# super-nintendo-forever.net
KiCad netlist of a schematic drawn in EAGLE
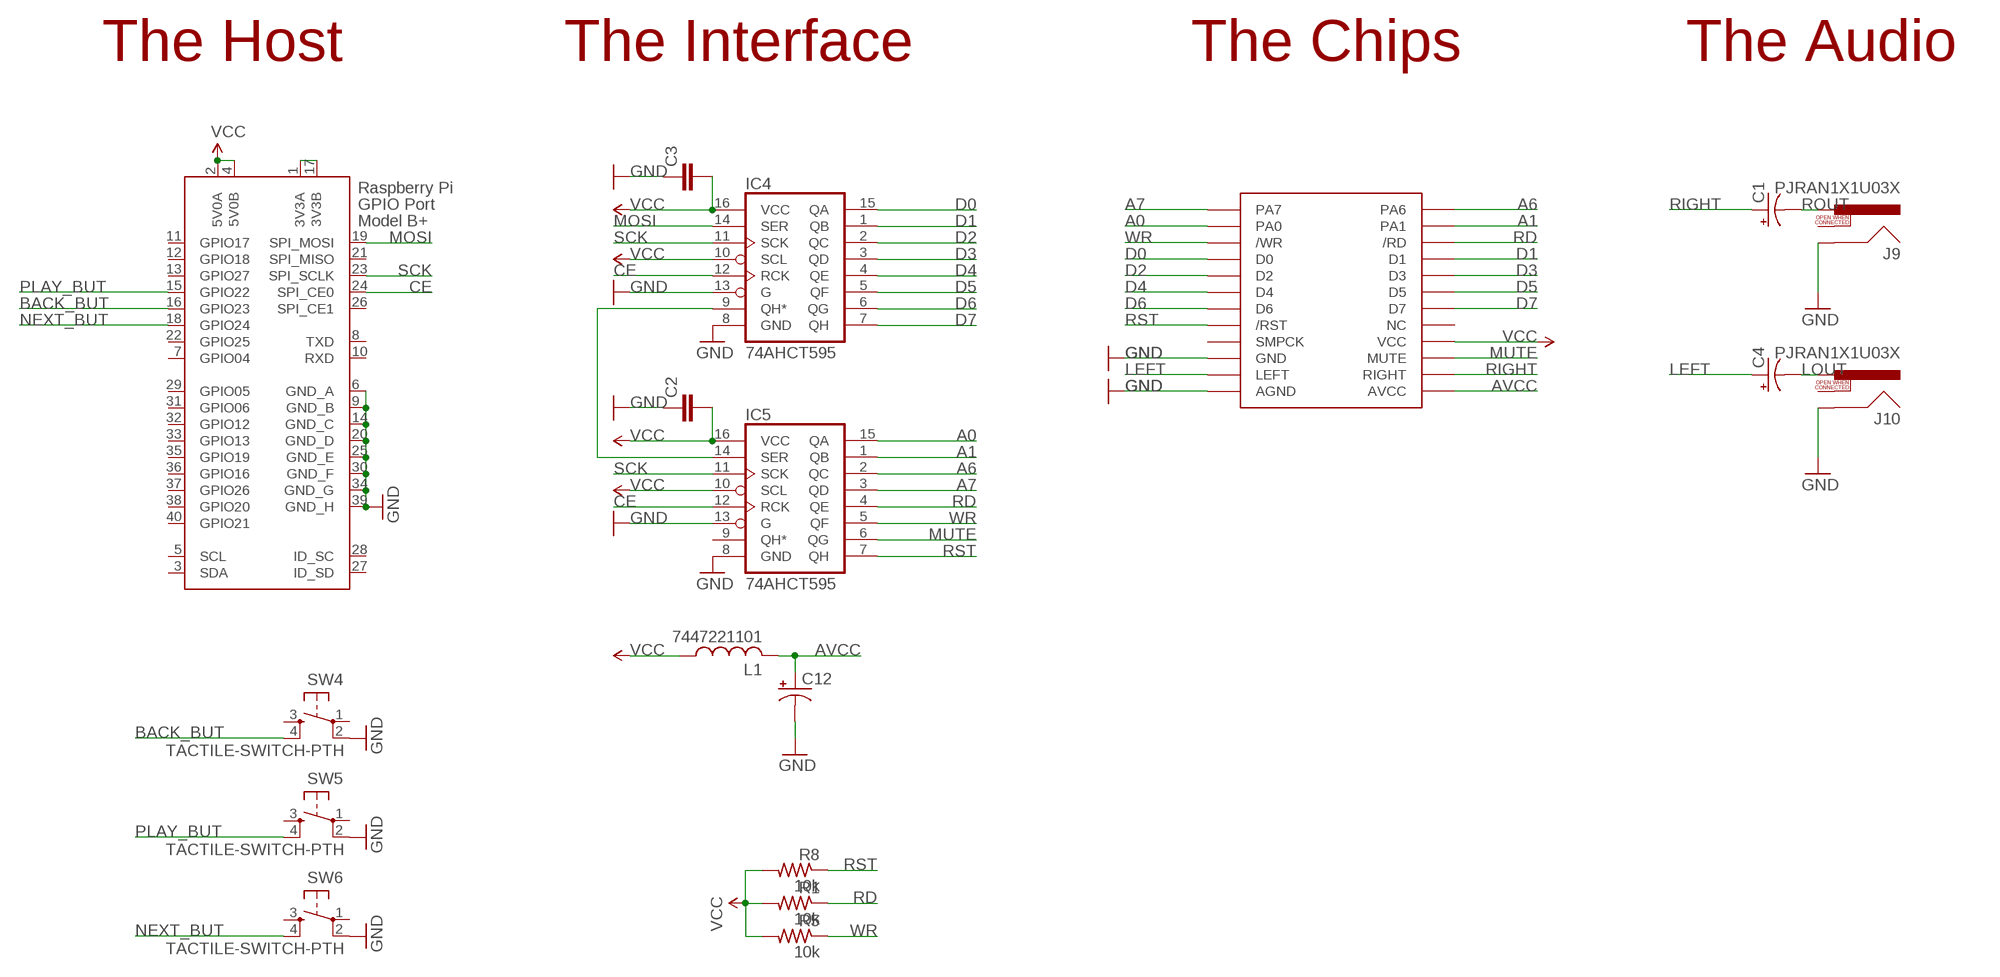
[diagram p0: schematic, sheet 1]

(export (version "E")
  (design (tool "Eeschema 10.0.6"))
  (components
    (comp (ref "C1")
      (value "CPOL-USE2-4")
      (footprint "eagle-import:E2-4")
      (libsource (lib "eagle-import") (part "CPOL-USE2-4"))
    )
    (comp (ref "C2")
      (value "C-EU025-024X044")
      (footprint "eagle-import:C025-024X044")
      (libsource (lib "eagle-import") (part "C-EU025-024X044"))
    )
    (comp (ref "C3")
      (value "C-EU025-024X044")
      (footprint "eagle-import:C025-024X044")
      (libsource (lib "eagle-import") (part "C-EU025-024X044"))
    )
    (comp (ref "C4")
      (value "CPOL-USE2-4")
      (footprint "eagle-import:E2-4")
      (libsource (lib "eagle-import") (part "CPOL-USE2-4"))
    )
    (comp (ref "C12")
      (value "CPOL-USE2-4")
      (footprint "eagle-import:E2-4")
      (libsource (lib "eagle-import") (part "CPOL-USE2-4"))
    )
    (comp (ref "IC4")
      (value "74AHCT595")
      (footprint "eagle-import:DIL16")
      (libsource (lib "eagle-import") (part "74595NLS"))
    )
    (comp (ref "IC5")
      (value "74AHCT595")
      (footprint "eagle-import:DIL16")
      (libsource (lib "eagle-import") (part "74595NLS"))
    )
    (comp (ref "J9")
      (value "PJRAN1X1U03X")
      (footprint "eagle-import:RCA")
      (libsource (lib "eagle-import") (part "RCA"))
    )
    (comp (ref "J10")
      (value "PJRAN1X1U03X")
      (footprint "eagle-import:RCA")
      (libsource (lib "eagle-import") (part "RCA"))
    )
    (comp (ref "L1")
      (value "7447221101")
      (footprint "eagle-import:12MMINDUCTOR")
      (libsource (lib "eagle-import") (part "L"))
    )
    (comp (ref "R1")
      (value "10k")
      (footprint "eagle-import:0207_7")
      (libsource (lib "eagle-import") (part "R-US_0207/7"))
    )
    (comp (ref "R5")
      (value "10k")
      (footprint "eagle-import:0207_7")
      (libsource (lib "eagle-import") (part "R-US_0207/7"))
    )
    (comp (ref "R8")
      (value "10k")
      (footprint "eagle-import:0207_7")
      (libsource (lib "eagle-import") (part "R-US_0207/7"))
    )
    (comp (ref "SW4")
      (value "TACTILE-SWITCH-PTH")
      (footprint "eagle-import:TAC-SWITCH-PTH")
      (libsource (lib "eagle-import") (part "TACTILE-SWITCH-PTH"))
    )
    (comp (ref "SW5")
      (value "TACTILE-SWITCH-PTH")
      (footprint "eagle-import:TAC-SWITCH-PTH")
      (libsource (lib "eagle-import") (part "TACTILE-SWITCH-PTH"))
    )
    (comp (ref "SW6")
      (value "TACTILE-SWITCH-PTH")
      (footprint "eagle-import:TAC-SWITCH-PTH")
      (libsource (lib "eagle-import") (part "TACTILE-SWITCH-PTH"))
    )
    (comp (ref "U$1")
      (value "APU2")
      (footprint "eagle-import:APU3")
      (libsource (lib "eagle-import") (part "APU2"))
    )
    (comp (ref "X2")
      (value "RASPI_BOARD_B+#_E4")
      (footprint "eagle-import:RASPI_BOARD_B+_EDGES_4DRILL")
      (libsource (lib "eagle-import") (part "RASPI_BOARD_B+#_E4"))
    )
  )
  (nets
    (net (code "1") (name "/A0") (class "Default")
      (node (ref "IC5") (pin "15") (pinfunction "QA_15") (pintype "tri_state"))
      (node (ref "U$1") (pin "A0") (pinfunction "PA0_A0") (pintype "bidirectional"))
    )
    (net (code "2") (name "/A1") (class "Default")
      (node (ref "IC5") (pin "1") (pinfunction "QB_1") (pintype "tri_state"))
      (node (ref "U$1") (pin "PA1") (pinfunction "PA1_PA1") (pintype "bidirectional"))
    )
    (net (code "3") (name "/A6") (class "Default")
      (node (ref "IC5") (pin "2") (pinfunction "QC_2") (pintype "tri_state"))
      (node (ref "U$1") (pin "PA6") (pinfunction "PA6_PA6") (pintype "bidirectional"))
    )
    (net (code "4") (name "/A7") (class "Default")
      (node (ref "IC5") (pin "3") (pinfunction "QD_3") (pintype "tri_state"))
      (node (ref "U$1") (pin "A7") (pinfunction "PA7_A7") (pintype "bidirectional"))
    )
    (net (code "5") (name "/AVCC") (class "Default")
      (node (ref "C12") (pin "+") (pinfunction "+_+") (pintype "passive"))
      (node (ref "L1") (pin "3") (pinfunction "2_3") (pintype "passive"))
      (node (ref "U$1") (pin "VCCA") (pinfunction "AVCC_VCCA") (pintype "bidirectional"))
    )
    (net (code "6") (name "/BACK_BUT") (class "Default")
      (node (ref "SW4") (pin "4") (pinfunction "4_4") (pintype "passive"))
      (node (ref "X2") (pin "16") (pinfunction "GPIO23_16") (pintype "bidirectional"))
    )
    (net (code "7") (name "/CE") (class "Default")
      (node (ref "IC4") (pin "12") (pinfunction "RCK_12") (pintype "input"))
      (node (ref "IC5") (pin "12") (pinfunction "RCK_12") (pintype "input"))
      (node (ref "X2") (pin "24") (pinfunction "SPI_CE0_24") (pintype "bidirectional"))
    )
    (net (code "8") (name "/D0") (class "Default")
      (node (ref "IC4") (pin "15") (pinfunction "QA_15") (pintype "tri_state"))
      (node (ref "U$1") (pin "D0") (pinfunction "D0_D0") (pintype "bidirectional"))
    )
    (net (code "9") (name "/D1") (class "Default")
      (node (ref "IC4") (pin "1") (pinfunction "QB_1") (pintype "tri_state"))
      (node (ref "U$1") (pin "D1") (pinfunction "D1_D1") (pintype "bidirectional"))
    )
    (net (code "10") (name "/D2") (class "Default")
      (node (ref "IC4") (pin "2") (pinfunction "QC_2") (pintype "tri_state"))
      (node (ref "U$1") (pin "D2") (pinfunction "D2_D2") (pintype "bidirectional"))
    )
    (net (code "11") (name "/D3") (class "Default")
      (node (ref "IC4") (pin "3") (pinfunction "QD_3") (pintype "tri_state"))
      (node (ref "U$1") (pin "D3") (pinfunction "D3_D3") (pintype "bidirectional"))
    )
    (net (code "12") (name "/D4") (class "Default")
      (node (ref "IC4") (pin "4") (pinfunction "QE_4") (pintype "tri_state"))
      (node (ref "U$1") (pin "D4") (pinfunction "D4_D4") (pintype "bidirectional"))
    )
    (net (code "13") (name "/D5") (class "Default")
      (node (ref "IC4") (pin "5") (pinfunction "QF_5") (pintype "tri_state"))
      (node (ref "U$1") (pin "D5") (pinfunction "D5_D5") (pintype "bidirectional"))
    )
    (net (code "14") (name "/D6") (class "Default")
      (node (ref "IC4") (pin "6") (pinfunction "QG_6") (pintype "tri_state"))
      (node (ref "U$1") (pin "D6") (pinfunction "D6_D6") (pintype "bidirectional"))
    )
    (net (code "15") (name "/D7") (class "Default")
      (node (ref "IC4") (pin "7") (pinfunction "QH_7") (pintype "tri_state"))
      (node (ref "U$1") (pin "D7") (pinfunction "D7_D7") (pintype "bidirectional"))
    )
    (net (code "16") (name "/LEFT") (class "Default")
      (node (ref "C4") (pin "+") (pinfunction "+_+") (pintype "passive"))
      (node (ref "U$1") (pin "OUTL") (pinfunction "LEFT_OUTL") (pintype "bidirectional"))
    )
    (net (code "17") (name "/LOUT") (class "Default")
      (node (ref "C4") (pin "-") (pinfunction "-_-") (pintype "passive"))
      (node (ref "J10") (pin "PIN") (pinfunction "PIN_PIN") (pintype "bidirectional"))
    )
    (net (code "18") (name "/MOSI") (class "Default")
      (node (ref "IC4") (pin "14") (pinfunction "SER_14") (pintype "input"))
      (node (ref "X2") (pin "19") (pinfunction "SPI_MOSI_19") (pintype "bidirectional"))
    )
    (net (code "19") (name "/MUTE") (class "Default")
      (node (ref "IC5") (pin "6") (pinfunction "QG_6") (pintype "tri_state"))
      (node (ref "U$1") (pin "MUTE") (pinfunction "MUTE_MUTE") (pintype "bidirectional"))
    )
    (net (code "20") (name "/NEXT_BUT") (class "Default")
      (node (ref "SW6") (pin "4") (pinfunction "4_4") (pintype "passive"))
      (node (ref "X2") (pin "18") (pinfunction "GPIO24_18") (pintype "bidirectional"))
    )
    (net (code "21") (name "/PLAY_BUT") (class "Default")
      (node (ref "SW5") (pin "4") (pinfunction "4_4") (pintype "passive"))
      (node (ref "X2") (pin "15") (pinfunction "GPIO22_15") (pintype "bidirectional"))
    )
    (net (code "22") (name "/RD") (class "Default")
      (node (ref "IC5") (pin "4") (pinfunction "QE_4") (pintype "tri_state"))
      (node (ref "R1") (pin "1") (pinfunction "1_1") (pintype "passive"))
      (node (ref "U$1") (pin "!RD") (pinfunction "/RD_!RD") (pintype "bidirectional"))
    )
    (net (code "23") (name "/RIGHT") (class "Default")
      (node (ref "C1") (pin "+") (pinfunction "+_+") (pintype "passive"))
      (node (ref "U$1") (pin "OUTR") (pinfunction "RIGHT_OUTR") (pintype "bidirectional"))
    )
    (net (code "24") (name "/ROUT") (class "Default")
      (node (ref "C1") (pin "-") (pinfunction "-_-") (pintype "passive"))
      (node (ref "J9") (pin "PIN") (pinfunction "PIN_PIN") (pintype "bidirectional"))
    )
    (net (code "25") (name "/RST") (class "Default")
      (node (ref "IC5") (pin "7") (pinfunction "QH_7") (pintype "tri_state"))
      (node (ref "R8") (pin "1") (pinfunction "1_1") (pintype "passive"))
      (node (ref "U$1") (pin "!RST") (pinfunction "/RST_!RST") (pintype "bidirectional"))
    )
    (net (code "26") (name "/SCK") (class "Default")
      (node (ref "IC4") (pin "11") (pinfunction "SCK_11") (pintype "input"))
      (node (ref "IC5") (pin "11") (pinfunction "SCK_11") (pintype "input"))
      (node (ref "X2") (pin "23") (pinfunction "SPI_SCLK_23") (pintype "bidirectional"))
    )
    (net (code "27") (name "/WR") (class "Default")
      (node (ref "IC5") (pin "5") (pinfunction "QF_5") (pintype "tri_state"))
      (node (ref "R5") (pin "1") (pinfunction "1_1") (pintype "passive"))
      (node (ref "U$1") (pin "!WR") (pinfunction "/WR_!WR") (pintype "bidirectional"))
    )
    (net (code "28") (name "GND") (class "Default")
      (node (ref "C12") (pin "-") (pinfunction "-_-") (pintype "passive"))
      (node (ref "C2") (pin "1") (pinfunction "1_1") (pintype "passive"))
      (node (ref "C3") (pin "1") (pinfunction "1_1") (pintype "passive"))
      (node (ref "IC4") (pin "13") (pinfunction "G_13") (pintype "input"))
      (node (ref "IC4") (pin "8") (pinfunction "GND_8") (pintype "power_in"))
      (node (ref "IC5") (pin "13") (pinfunction "G_13") (pintype "input"))
      (node (ref "IC5") (pin "8") (pinfunction "GND_8") (pintype "power_in"))
      (node (ref "J10") (pin "SHELL") (pinfunction "SHELL_SHELL") (pintype "bidirectional"))
      (node (ref "J9") (pin "SHELL") (pinfunction "SHELL_SHELL") (pintype "bidirectional"))
      (node (ref "SW4") (pin "2") (pinfunction "2_2") (pintype "passive"))
      (node (ref "SW5") (pin "2") (pinfunction "2_2") (pintype "passive"))
      (node (ref "SW6") (pin "2") (pinfunction "2_2") (pintype "passive"))
      (node (ref "U$1") (pin "GND") (pinfunction "GND_GND") (pintype "bidirectional"))
      (node (ref "U$1") (pin "GNDA") (pinfunction "AGND_GNDA") (pintype "bidirectional"))
      (node (ref "U$1") (pin "P$25") (pinfunction "GND_P$25") (pintype "bidirectional"))
      (node (ref "U$1") (pin "P$26") (pinfunction "GND_P$26") (pintype "bidirectional"))
      (node (ref "X2") (pin "14") (pinfunction "GND_C_14") (pintype "power_in"))
      (node (ref "X2") (pin "20") (pinfunction "GND_D_20") (pintype "power_in"))
      (node (ref "X2") (pin "25") (pinfunction "GND_E_25") (pintype "power_in"))
      (node (ref "X2") (pin "30") (pinfunction "GND_F_30") (pintype "power_in"))
      (node (ref "X2") (pin "34") (pinfunction "GND_G_34") (pintype "power_in"))
      (node (ref "X2") (pin "39") (pinfunction "GND_H_39") (pintype "power_in"))
      (node (ref "X2") (pin "6") (pinfunction "GND_A_6") (pintype "power_in"))
      (node (ref "X2") (pin "9") (pinfunction "GND_B_9") (pintype "power_in"))
    )
    (net (code "29") (name "Net-(IC4-QH*)") (class "Default")
      (node (ref "IC4") (pin "9") (pinfunction "QH*_9") (pintype "tri_state"))
      (node (ref "IC5") (pin "14") (pinfunction "SER_14") (pintype "input"))
    )
    (net (code "30") (name "Net-(X2-3V3A)") (class "Default")
      (node (ref "X2") (pin "1") (pinfunction "3V3A_1") (pintype "power_in"))
      (node (ref "X2") (pin "17") (pinfunction "3V3B_17") (pintype "power_in"))
    )
    (net (code "31") (name "VCC") (class "Default")
      (node (ref "C2") (pin "2") (pinfunction "2_2") (pintype "passive"))
      (node (ref "C3") (pin "2") (pinfunction "2_2") (pintype "passive"))
      (node (ref "IC4") (pin "10") (pinfunction "SCL_10") (pintype "input"))
      (node (ref "IC4") (pin "16") (pinfunction "VCC_16") (pintype "power_in"))
      (node (ref "IC5") (pin "10") (pinfunction "SCL_10") (pintype "input"))
      (node (ref "IC5") (pin "16") (pinfunction "VCC_16") (pintype "power_in"))
      (node (ref "L1") (pin "2") (pinfunction "1_2") (pintype "passive"))
      (node (ref "R1") (pin "2") (pinfunction "2_2") (pintype "passive"))
      (node (ref "R5") (pin "2") (pinfunction "2_2") (pintype "passive"))
      (node (ref "R8") (pin "2") (pinfunction "2_2") (pintype "passive"))
      (node (ref "U$1") (pin "VCC") (pinfunction "VCC_VCC") (pintype "bidirectional"))
      (node (ref "X2") (pin "2") (pinfunction "5V0A_2") (pintype "power_in"))
      (node (ref "X2") (pin "4") (pinfunction "5V0B_4") (pintype "power_in"))
    )
    (net (code "32") (name "unconnected-(IC5-QH*-Pad9)") (class "Default")
      (node (ref "IC5") (pin "9") (pinfunction "QH*_9") (pintype "tri_state"))
    )
    (net (code "33") (name "unconnected-(J9-PadSWITCH)") (class "Default")
      (node (ref "J9") (pin "SWITCH") (pinfunction "SWITCH_SWITCH") (pintype "bidirectional"))
    )
    (net (code "34") (name "unconnected-(J10-PadSWITCH)") (class "Default")
      (node (ref "J10") (pin "SWITCH") (pinfunction "SWITCH_SWITCH") (pintype "bidirectional"))
    )
    (net (code "35") (name "unconnected-(SW4-Pad1)") (class "Default")
      (node (ref "SW4") (pin "1") (pinfunction "1_1") (pintype "passive"))
    )
    (net (code "36") (name "unconnected-(SW4-Pad3)") (class "Default")
      (node (ref "SW4") (pin "3") (pinfunction "3_3") (pintype "passive"))
    )
    (net (code "37") (name "unconnected-(SW5-Pad1)") (class "Default")
      (node (ref "SW5") (pin "1") (pinfunction "1_1") (pintype "passive"))
    )
    (net (code "38") (name "unconnected-(SW5-Pad3)") (class "Default")
      (node (ref "SW5") (pin "3") (pinfunction "3_3") (pintype "passive"))
    )
    (net (code "39") (name "unconnected-(SW6-Pad1)") (class "Default")
      (node (ref "SW6") (pin "1") (pinfunction "1_1") (pintype "passive"))
    )
    (net (code "40") (name "unconnected-(SW6-Pad3)") (class "Default")
      (node (ref "SW6") (pin "3") (pinfunction "3_3") (pintype "passive"))
    )
    (net (code "41") (name "unconnected-(U$1-PadNC)") (class "Default")
      (node (ref "U$1") (pin "NC") (pinfunction "NC_NC") (pintype "bidirectional"))
    )
    (net (code "42") (name "unconnected-(U$1-SMPCK-PadSMPCLK)") (class "Default")
      (node (ref "U$1") (pin "SMPCLK") (pinfunction "SMPCK_SMPCLK") (pintype "bidirectional"))
    )
    (net (code "43") (name "unconnected-(X2-GPIO04-Pad7)") (class "Default")
      (node (ref "X2") (pin "7") (pinfunction "GPIO04_7") (pintype "bidirectional"))
    )
    (net (code "44") (name "unconnected-(X2-GPIO05-Pad29)") (class "Default")
      (node (ref "X2") (pin "29") (pinfunction "GPIO05_29") (pintype "no_connect"))
    )
    (net (code "45") (name "unconnected-(X2-GPIO06-Pad31)") (class "Default")
      (node (ref "X2") (pin "31") (pinfunction "GPIO06_31") (pintype "no_connect"))
    )
    (net (code "46") (name "unconnected-(X2-GPIO12-Pad32)") (class "Default")
      (node (ref "X2") (pin "32") (pinfunction "GPIO12_32") (pintype "no_connect"))
    )
    (net (code "47") (name "unconnected-(X2-GPIO13-Pad33)") (class "Default")
      (node (ref "X2") (pin "33") (pinfunction "GPIO13_33") (pintype "no_connect"))
    )
    (net (code "48") (name "unconnected-(X2-GPIO16-Pad36)") (class "Default")
      (node (ref "X2") (pin "36") (pinfunction "GPIO16_36") (pintype "no_connect"))
    )
    (net (code "49") (name "unconnected-(X2-GPIO17-Pad11)") (class "Default")
      (node (ref "X2") (pin "11") (pinfunction "GPIO17_11") (pintype "bidirectional"))
    )
    (net (code "50") (name "unconnected-(X2-GPIO18-Pad12)") (class "Default")
      (node (ref "X2") (pin "12") (pinfunction "GPIO18_12") (pintype "bidirectional"))
    )
    (net (code "51") (name "unconnected-(X2-GPIO19-Pad35)") (class "Default")
      (node (ref "X2") (pin "35") (pinfunction "GPIO19_35") (pintype "no_connect"))
    )
    (net (code "52") (name "unconnected-(X2-GPIO20-Pad38)") (class "Default")
      (node (ref "X2") (pin "38") (pinfunction "GPIO20_38") (pintype "no_connect"))
    )
    (net (code "53") (name "unconnected-(X2-GPIO21-Pad40)") (class "Default")
      (node (ref "X2") (pin "40") (pinfunction "GPIO21_40") (pintype "no_connect"))
    )
    (net (code "54") (name "unconnected-(X2-GPIO25-Pad22)") (class "Default")
      (node (ref "X2") (pin "22") (pinfunction "GPIO25_22") (pintype "bidirectional"))
    )
    (net (code "55") (name "unconnected-(X2-GPIO26-Pad37)") (class "Default")
      (node (ref "X2") (pin "37") (pinfunction "GPIO26_37") (pintype "no_connect"))
    )
    (net (code "56") (name "unconnected-(X2-GPIO27-Pad13)") (class "Default")
      (node (ref "X2") (pin "13") (pinfunction "GPIO27_13") (pintype "bidirectional"))
    )
    (net (code "57") (name "unconnected-(X2-ID_SC-Pad28)") (class "Default")
      (node (ref "X2") (pin "28") (pinfunction "ID_SC_28") (pintype "no_connect"))
    )
    (net (code "58") (name "unconnected-(X2-ID_SD-Pad27)") (class "Default")
      (node (ref "X2") (pin "27") (pinfunction "ID_SD_27") (pintype "no_connect"))
    )
    (net (code "59") (name "unconnected-(X2-RXD-Pad10)") (class "Default")
      (node (ref "X2") (pin "10") (pinfunction "RXD_10") (pintype "bidirectional"))
    )
    (net (code "60") (name "unconnected-(X2-SCL-Pad5)") (class "Default")
      (node (ref "X2") (pin "5") (pinfunction "SCL_5") (pintype "bidirectional"))
    )
    (net (code "61") (name "unconnected-(X2-SDA-Pad3)") (class "Default")
      (node (ref "X2") (pin "3") (pinfunction "SDA_3") (pintype "bidirectional"))
    )
    (net (code "62") (name "unconnected-(X2-SPI_CE1-Pad26)") (class "Default")
      (node (ref "X2") (pin "26") (pinfunction "SPI_CE1_26") (pintype "bidirectional"))
    )
    (net (code "63") (name "unconnected-(X2-SPI_MISO-Pad21)") (class "Default")
      (node (ref "X2") (pin "21") (pinfunction "SPI_MISO_21") (pintype "bidirectional"))
    )
    (net (code "64") (name "unconnected-(X2-TXD-Pad8)") (class "Default")
      (node (ref "X2") (pin "8") (pinfunction "TXD_8") (pintype "bidirectional"))
    )
  )
)
